# Sheet1.net
KiCad netlist of a schematic drawn in Altium Designer
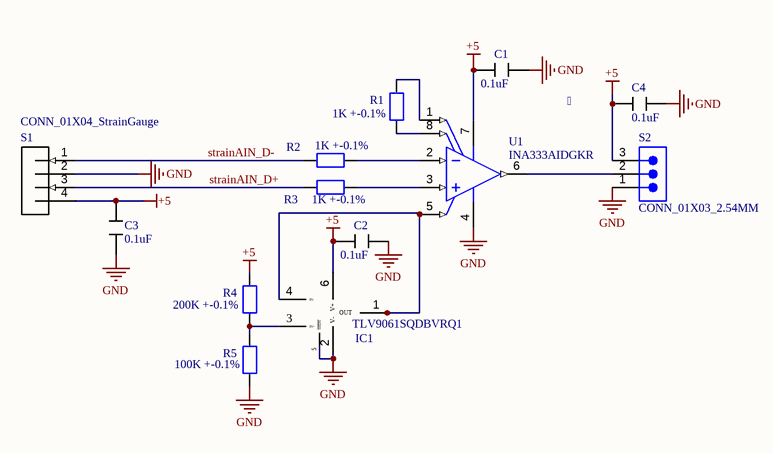
[diagram p0: Sheet1.SchDoc]

(export (version "E")
  (design (tool "Eeschema 10.0.6"))
  (components
    (comp (ref "C1")
      (value "0.1uF")
      (footprint "CAP_0805")
      (description "Generic 0805 component")
      (fields
        (field (name "MANUFACTURER") "YAGEO")
        (field (name "MANUFACTURER PART NUMBER") "CC0805JRNPO9BN250")
      )
      (libsource (lib "GenericSchematic-library") (part "CAP_0805"))
    )
    (comp (ref "C2")
      (value "0.1uF")
      (footprint "CAP_0805")
      (description "Generic 0805 component")
      (fields
        (field (name "MANUFACTURER") "YAGEO")
        (field (name "MANUFACTURER PART NUMBER") "CC0805JRNPO9BN250")
      )
      (libsource (lib "GenericSchematic-library") (part "CAP_0805"))
    )
    (comp (ref "C3")
      (value "0.1uF")
      (footprint "CAP_0805")
      (description "Generic 0805 component")
      (fields
        (field (name "MANUFACTURER") "YAGEO")
        (field (name "MANUFACTURER PART NUMBER") "CC0805JRNPO9BN250")
      )
      (libsource (lib "GenericSchematic-library") (part "CAP_0805"))
    )
    (comp (ref "C4")
      (value "0.1uF")
      (footprint "CAP_0805")
      (description "Generic 0805 component")
      (fields
        (field (name "MANUFACTURER") "YAGEO")
        (field (name "MANUFACTURER PART NUMBER") "CC0805JRNPO9BN250")
      )
      (libsource (lib "GenericSchematic-library") (part "CAP_0805"))
    )
    (comp (ref "IC1")
      (value "TLV9061SQDBVRQ1")
      (footprint "Generic-Footprint-Library:SOT95P280X145-6N")
      (description "Integrated Circuit")
      (fields (field (name "MOUSER PART NUMBER") "595-TLV9061SQDBVRQ1"))
      (libsource (lib "GenericSchematic-library") (part "TLV9061SQDBVRQ1"))
    )
    (comp (ref "R1")
      (value "1K +-0.1%")
      (footprint "RES_0805")
      (description "RES_0805")
      (fields
        (field (name "MANUFACTURER PART NUMBER") "RNCS0805BKE1K00")
        (field (name "MANUFACTURER") "Stackpole Electronics Inc")
      )
      (libsource (lib "GenericSchematic-library") (part "RES_0805"))
    )
    (comp (ref "R2")
      (value "1K +-0.1%")
      (footprint "RES_0805")
      (description "RES_0805")
      (fields
        (field (name "MANUFACTURER PART NUMBER") "RNCS0805BKE1K00")
        (field (name "MANUFACTURER") "Stackpole Electronics Inc")
      )
      (libsource (lib "GenericSchematic-library") (part "RES_0805"))
    )
    (comp (ref "R3")
      (value "1K +-0.1%")
      (footprint "RES_0805")
      (description "RES_0805")
      (fields
        (field (name "MANUFACTURER PART NUMBER") "RNCS0805BKE1K00")
        (field (name "MANUFACTURER") "Stackpole Electronics Inc")
      )
      (libsource (lib "GenericSchematic-library") (part "RES_0805"))
    )
    (comp (ref "R4")
      (value "200K +-0.1%")
      (footprint "RES_0805")
      (description "RES_0805")
      (fields
        (field (name "MANUFACTURER PART NUMBER") "RN73R2ATTD2003B25")
        (field (name "MANUFACTURER") "KOA Speer Electronics, Inc.")
      )
      (libsource (lib "GenericSchematic-library") (part "RES_0805"))
    )
    (comp (ref "R5")
      (value "100K +-0.1%")
      (footprint "RES_0805")
      (description "RES_0805")
      (fields
        (field (name "MANUFACTURER PART NUMBER") "RNCS0805BKE100K")
        (field (name "MANUFACTURER") "Stackpole Electronics Inc")
      )
      (libsource (lib "GenericSchematic-library") (part "RES_0805"))
    )
    (comp (ref "S1")
      (value "CONN_01X04_StrainGauge")
      (footprint "CONN_01X04")
      (libsource (lib "GenericSchematic-library") (part "CONN_01X04_StrainGauge"))
    )
    (comp (ref "S2")
      (value "CONN_01X03_2.54MM")
      (footprint "61300311121")
      (libsource (lib "GenericSchematic-library") (part "CONN_01X03_2.54MM"))
    )
    (comp (ref "U1")
      (value "INA333AIDGKR")
      (footprint "DGK0008A_N")
      (fields (field (name "MANUFACTURER") "Texas Instruments"))
      (libsource (lib "Altium Content Vault") (part "TI-INAXXXXXX8"))
    )
  )
  (nets
    (net (code "1") (name "+5") (class "Default")
      (node (ref "C1") (pin "1") (pintype "passive"))
      (node (ref "C2") (pin "1") (pintype "passive"))
      (node (ref "C3") (pin "2") (pintype "passive"))
      (node (ref "C4") (pin "2") (pintype "passive"))
      (node (ref "IC1") (pin "6") (pinfunction "V+_6") (pintype "passive"))
      (node (ref "R4") (pin "2") (pintype "passive"))
      (node (ref "S1") (pin "4") (pintype "power_in"))
      (node (ref "S2") (pin "3") (pinfunction "3_3") (pintype "passive"))
      (node (ref "U1") (pin "7") (pinfunction "V+_7") (pintype "power_in"))
    )
    (net (code "2") (name "/strainAIN_D+") (class "Default")
      (node (ref "R3") (pin "2") (pintype "passive"))
      (node (ref "S1") (pin "3") (pintype "input"))
    )
    (net (code "3") (name "/strainAIN_D-") (class "Default")
      (node (ref "R2") (pin "2") (pintype "passive"))
      (node (ref "S1") (pin "1") (pintype "input"))
    )
    (net (code "4") (name "GND") (class "Default")
      (node (ref "C1") (pin "2") (pintype "passive"))
      (node (ref "C2") (pin "2") (pintype "passive"))
      (node (ref "C3") (pin "1") (pintype "passive"))
      (node (ref "C4") (pin "1") (pintype "passive"))
      (node (ref "IC1") (pin "2") (pinfunction "V-_2") (pintype "passive"))
      (node (ref "IC1") (pin "5") (pinfunction "~{SHDN}_5") (pintype "passive"))
      (node (ref "R5") (pin "1") (pintype "passive"))
      (node (ref "S1") (pin "2") (pintype "power_in"))
      (node (ref "S2") (pin "1") (pinfunction "1_1") (pintype "passive"))
      (node (ref "U1") (pin "4") (pinfunction "V-_4") (pintype "power_in"))
    )
    (net (code "5") (name "Net-(IC1-IN+)") (class "Default")
      (node (ref "IC1") (pin "3") (pinfunction "IN+_3") (pintype "passive"))
      (node (ref "R4") (pin "1") (pintype "passive"))
      (node (ref "R5") (pin "2") (pintype "passive"))
    )
    (net (code "6") (name "Net-(IC1-IN-)") (class "Default")
      (node (ref "IC1") (pin "1") (pinfunction "OUT_1") (pintype "passive"))
      (node (ref "IC1") (pin "4") (pinfunction "IN-_4") (pintype "passive"))
      (node (ref "U1") (pin "5") (pinfunction "REF_5") (pintype "input"))
    )
    (net (code "7") (name "Net-(R1-Pad1)") (class "Default")
      (node (ref "R1") (pin "1") (pintype "passive"))
      (node (ref "U1") (pin "8") (pinfunction "RG_8") (pintype "input"))
    )
    (net (code "8") (name "Net-(R1-Pad2)") (class "Default")
      (node (ref "R1") (pin "2") (pintype "passive"))
      (node (ref "U1") (pin "1") (pinfunction "RG_1") (pintype "input"))
    )
    (net (code "9") (name "Net-(U1-VIN+)") (class "Default")
      (node (ref "R3") (pin "1") (pintype "passive"))
      (node (ref "U1") (pin "3") (pinfunction "VIN+_3") (pintype "input"))
    )
    (net (code "10") (name "Net-(U1-VIN-)") (class "Default")
      (node (ref "R2") (pin "1") (pintype "passive"))
      (node (ref "U1") (pin "2") (pinfunction "VIN-_2") (pintype "input"))
    )
    (net (code "11") (name "Net-(U1-VOUT)") (class "Default")
      (node (ref "S2") (pin "2") (pinfunction "2_2") (pintype "passive"))
      (node (ref "U1") (pin "6") (pinfunction "VOUT_6") (pintype "output"))
    )
  )
)
